# msp430g2553.net
KiCad netlist of a schematic drawn in Altium Designer
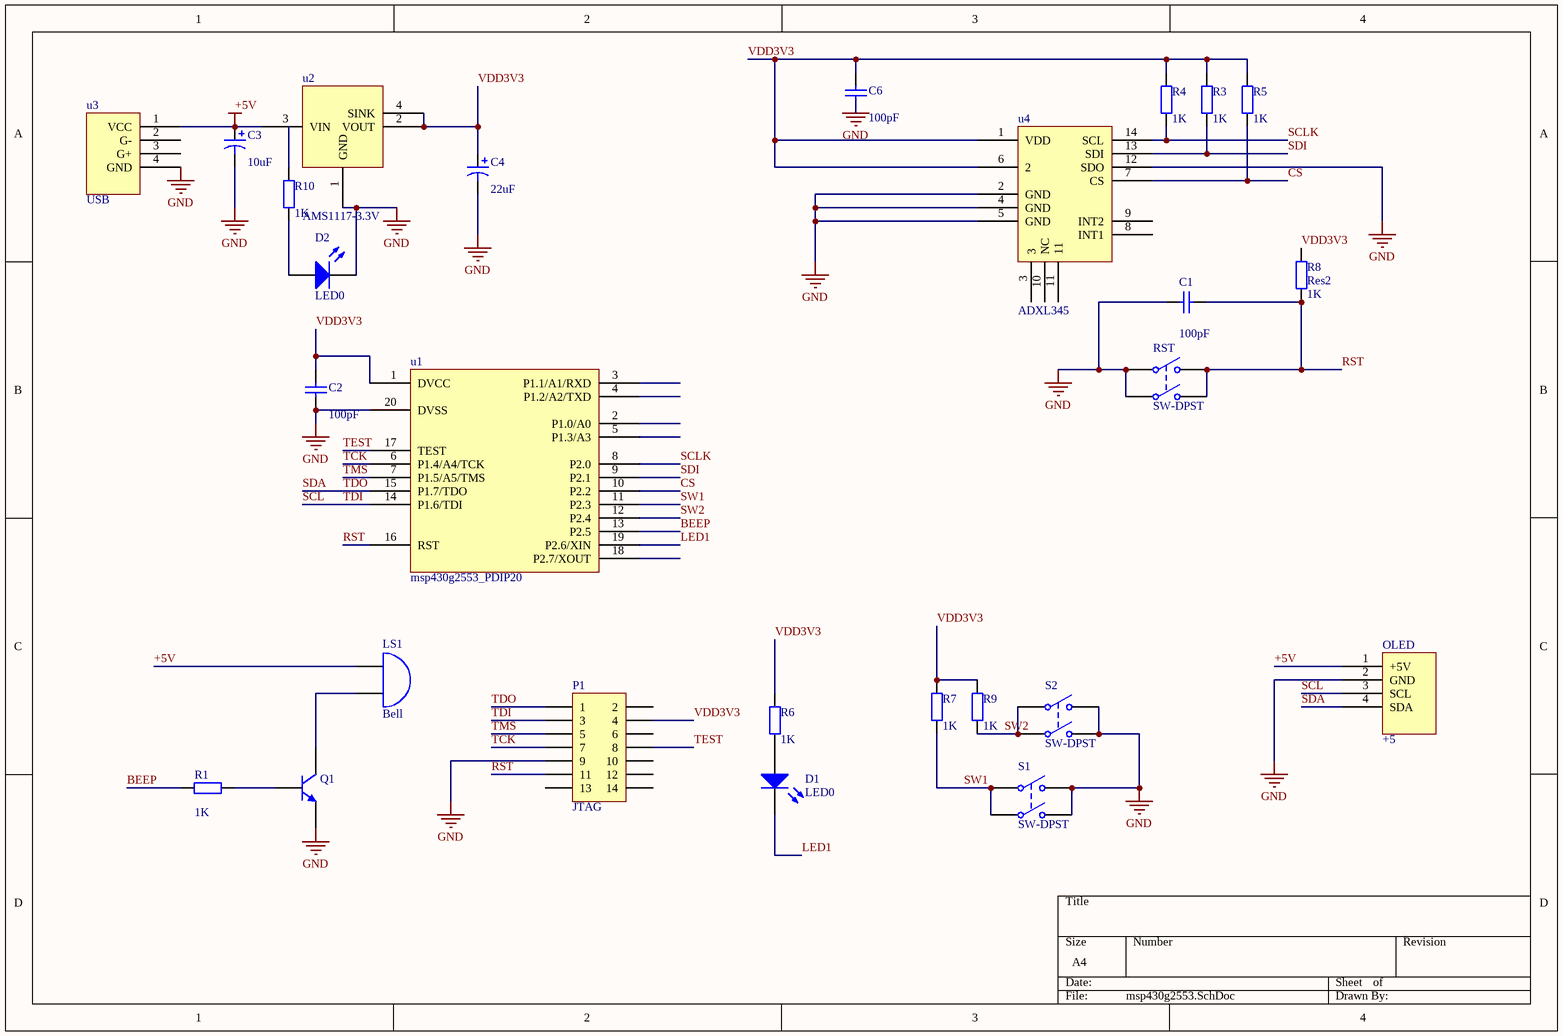
[diagram p0: msp430g2553.SchDoc]

(export (version "E")
  (design (tool "Eeschema 10.0.6"))
  (components
    (comp (ref "C1")
      (value "100pF")
      (footprint "6-0805_N")
      (description "Capacitor")
      (fields (field (name "Comment") "Cap") (field (name "PUBLISHER") "Altium Limited"))
      (libsource (lib "msp430g2553") (part "Cap"))
    )
    (comp (ref "C2")
      (value "100pF")
      (footprint "6-0805_N")
      (description "Capacitor")
      (fields (field (name "Comment") "Cap") (field (name "PUBLISHER") "Altium Limited"))
      (libsource (lib "msp430g2553") (part "Cap"))
    )
    (comp (ref "C3")
      (value "10uF")
      (footprint "6-0805_N - duplicate")
      (description "Polarized Capacitor (Axial)")
      (fields (field (name "Comment") "Cap Pol2") (field (name "PUBLISHER") "Altium Limited"))
      (libsource (lib "msp430g2553") (part "Cap Pol2"))
    )
    (comp (ref "C4")
      (value "22uF")
      (footprint "6-0805_N - duplicate")
      (description "Polarized Capacitor (Axial)")
      (fields (field (name "Comment") "Cap Pol2") (field (name "PUBLISHER") "Altium Limited"))
      (libsource (lib "msp430g2553") (part "Cap Pol2"))
    )
    (comp (ref "C6")
      (value "100pF")
      (footprint "6-0805_N")
      (description "Capacitor")
      (fields (field (name "Comment") "Cap") (field (name "PUBLISHER") "Altium Limited"))
      (libsource (lib "msp430g2553") (part "Cap"))
    )
    (comp (ref "D1")
      (value "LED0")
      (footprint "6-0805_N - duplicate")
      (description "Typical INFRARED GaAs LED")
      (fields (field (name "PUBLISHER") "Altium Limited"))
      (libsource (lib "msp430g2553") (part "LED0"))
    )
    (comp (ref "D2")
      (value "LED0")
      (footprint "6-0805_N - duplicate")
      (description "Typical INFRARED GaAs LED")
      (fields (field (name "PUBLISHER") "Altium Limited"))
      (libsource (lib "msp430g2553") (part "LED0"))
    )
    (comp (ref "LS1")
      (value "Bell")
      (footprint "bell")
      (description "Electrical Bell")
      (fields (field (name "PUBLISHER") "Altium Limited"))
      (libsource (lib "msp430g2553") (part "Bell"))
    )
    (comp (ref "OLED") (value "+5") (footprint "OLED") (libsource (lib "msp430g2553") (part "OLED")))
    (comp (ref "P1")
      (value "JTAG")
      (footprint "HDR2X7")
      (description "Header, 7-Pin, Dual row")
      (fields (field (name "PUBLISHER") "Altium Limited"))
      (libsource (lib "msp430g2553") (part "JTAG"))
    )
    (comp (ref "Q1")
      (value "NPN")
      (footprint "SOT23_N")
      (description "NPN Bipolar Transistor")
      (fields (field (name "PUBLISHER") "Altium Limited"))
      (libsource (lib "msp430g2553") (part "NPN"))
    )
    (comp (ref "R1")
      (value "1K")
      (footprint "6-0805_N")
      (description "Resistor")
      (fields (field (name "Comment") "Res2") (field (name "PUBLISHER") "Altium Limited"))
      (libsource (lib "") (part "Res2_1"))
    )
    (comp (ref "R3")
      (value "1K")
      (footprint "6-0805_N")
      (description "Resistor")
      (fields (field (name "Comment") "Res2") (field (name "PUBLISHER") "Altium Limited"))
      (libsource (lib "msp430g2553") (part "Res2"))
    )
    (comp (ref "R4")
      (value "1K")
      (footprint "6-0805_N")
      (description "Resistor")
      (fields (field (name "Comment") "Res2") (field (name "PUBLISHER") "Altium Limited"))
      (libsource (lib "msp430g2553") (part "Res2"))
    )
    (comp (ref "R5")
      (value "1K")
      (footprint "6-0805_N")
      (description "Resistor")
      (fields (field (name "Comment") "Res2") (field (name "PUBLISHER") "Altium Limited"))
      (libsource (lib "msp430g2553") (part "Res2"))
    )
    (comp (ref "R6")
      (value "1K")
      (footprint "6-0805_N")
      (description "Resistor")
      (fields (field (name "Comment") "Res2") (field (name "PUBLISHER") "Altium Limited"))
      (libsource (lib "msp430g2553") (part "Res2"))
    )
    (comp (ref "R7")
      (value "1K")
      (footprint "6-0805_N")
      (description "Resistor")
      (fields (field (name "Comment") "Res2") (field (name "PUBLISHER") "Altium Limited"))
      (libsource (lib "msp430g2553") (part "Res2"))
    )
    (comp (ref "R8")
      (value "Res2")
      (footprint "6-0805_N")
      (description "Resistor")
      (fields (field (name "ALTIUM_VALUE") "1K") (field (name "PUBLISHER") "Altium Limited"))
      (libsource (lib "msp430g2553") (part "Res2"))
    )
    (comp (ref "R9")
      (value "1K")
      (footprint "6-0805_N")
      (description "Resistor")
      (fields (field (name "Comment") "Res2") (field (name "PUBLISHER") "Altium Limited"))
      (libsource (lib "msp430g2553") (part "Res2"))
    )
    (comp (ref "R10")
      (value "1K")
      (footprint "6-0805_N")
      (description "Resistor")
      (fields (field (name "Comment") "Res2") (field (name "PUBLISHER") "Altium Limited"))
      (libsource (lib "msp430g2553") (part "Res2"))
    )
    (comp (ref "RST")
      (value "SW-DPST")
      (footprint "DPST-4")
      (description "Double-Pole, Single-Throw Switch")
      (fields (field (name "PUBLISHER") "Altium Limited"))
      (libsource (lib "msp430g2553") (part "SW-DPST"))
    )
    (comp (ref "S1")
      (value "SW-DPST")
      (footprint "DPST-4")
      (description "Double-Pole, Single-Throw Switch")
      (fields (field (name "PUBLISHER") "Altium Limited"))
      (libsource (lib "msp430g2553") (part "SW-DPST"))
    )
    (comp (ref "S2")
      (value "SW-DPST")
      (footprint "DPST-4")
      (description "Double-Pole, Single-Throw Switch")
      (fields (field (name "PUBLISHER") "Altium Limited"))
      (libsource (lib "msp430g2553") (part "SW-DPST"))
    )
    (comp (ref "u1")
      (value "msp430g2553_PDIP20")
      (footprint "DIP20")
      (libsource (lib "msp430g2553") (part "msp430g2553_PDIP20"))
    )
    (comp (ref "u2")
      (value "AMS1117-3.3V")
      (footprint "SOT223_N")
      (libsource (lib "msp430g2553") (part "AMS1117-3.3V"))
    )
    (comp (ref "u3") (value "USB") (footprint "USB2.5-2H4") (libsource (lib "msp430g2553") (part "USB")))
    (comp (ref "u4") (value "ADXL345") (footprint "ADXL345") (libsource (lib "msp430g2553") (part "ADXL345")))
  )
  (nets
    (net (code "1") (name "+5V") (class "Default")
      (node (ref "C3") (pin "2") (pinfunction "2_2") (pintype "passive"))
      (node (ref "LS1") (pin "1") (pinfunction "A_1") (pintype "passive"))
      (node (ref "OLED") (pin "1") (pinfunction "+5V_1") (pintype "passive"))
      (node (ref "u2") (pin "3") (pinfunction "VIN_3") (pintype "passive"))
      (node (ref "u3") (pin "1") (pinfunction "VCC_1") (pintype "passive"))
    )
    (net (code "2") (name "/BEEP") (class "Default")
      (node (ref "R1") (pin "1") (pinfunction "1_1") (pintype "passive"))
      (node (ref "u1") (pin "13") (pinfunction "P2.5_13") (pintype "passive"))
    )
    (net (code "3") (name "/CS") (class "Default")
      (node (ref "R5") (pin "1") (pinfunction "1_1") (pintype "passive"))
      (node (ref "u1") (pin "10") (pinfunction "P2.2_10") (pintype "passive"))
      (node (ref "u4") (pin "7") (pinfunction "CS_7") (pintype "passive"))
    )
    (net (code "4") (name "/LED1") (class "Default")
      (node (ref "D1") (pin "2") (pinfunction "K_2") (pintype "passive"))
      (node (ref "u1") (pin "19") (pinfunction "P2.6/XIN_19") (pintype "passive"))
    )
    (net (code "5") (name "/RST") (class "Default")
      (node (ref "C1") (pin "2") (pinfunction "2_2") (pintype "passive"))
      (node (ref "P1") (pin "11") (pinfunction "11_11") (pintype "passive"))
      (node (ref "R8") (pin "1") (pinfunction "1_1") (pintype "passive"))
      (node (ref "RST") (pin "3") (pinfunction "NO1_3") (pintype "passive"))
      (node (ref "RST") (pin "4") (pinfunction "NO2_4") (pintype "passive"))
      (node (ref "u1") (pin "16") (pinfunction "RST_16") (pintype "passive"))
    )
    (net (code "6") (name "/SCL") (class "Default")
      (node (ref "OLED") (pin "3") (pinfunction "SCL_3") (pintype "passive"))
      (node (ref "P1") (pin "3") (pinfunction "3_3") (pintype "passive"))
      (node (ref "u1") (pin "14") (pinfunction "P1.6/TDI_14") (pintype "passive"))
    )
    (net (code "7") (name "/SCLK") (class "Default")
      (node (ref "R4") (pin "1") (pinfunction "1_1") (pintype "passive"))
      (node (ref "u1") (pin "8") (pinfunction "P2.0_8") (pintype "passive"))
      (node (ref "u4") (pin "14") (pinfunction "SCL_14") (pintype "passive"))
    )
    (net (code "8") (name "/SDA") (class "Default")
      (node (ref "OLED") (pin "4") (pinfunction "SDA_4") (pintype "passive"))
      (node (ref "P1") (pin "1") (pinfunction "1_1") (pintype "passive"))
      (node (ref "u1") (pin "15") (pinfunction "P1.7/TDO_15") (pintype "passive"))
    )
    (net (code "9") (name "/SDI") (class "Default")
      (node (ref "R3") (pin "1") (pinfunction "1_1") (pintype "passive"))
      (node (ref "u1") (pin "9") (pinfunction "P2.1_9") (pintype "passive"))
      (node (ref "u4") (pin "13") (pinfunction "SDI_13") (pintype "passive"))
    )
    (net (code "10") (name "/SW1") (class "Default")
      (node (ref "R7") (pin "1") (pinfunction "1_1") (pintype "passive"))
      (node (ref "S1") (pin "1") (pinfunction "COMMON1_1") (pintype "passive"))
      (node (ref "S1") (pin "2") (pinfunction "COMMON2_2") (pintype "passive"))
      (node (ref "u1") (pin "11") (pinfunction "P2.3_11") (pintype "passive"))
    )
    (net (code "11") (name "/SW2") (class "Default")
      (node (ref "R9") (pin "1") (pinfunction "1_1") (pintype "passive"))
      (node (ref "S2") (pin "1") (pinfunction "COMMON1_1") (pintype "passive"))
      (node (ref "S2") (pin "2") (pinfunction "COMMON2_2") (pintype "passive"))
      (node (ref "u1") (pin "12") (pinfunction "P2.4_12") (pintype "passive"))
    )
    (net (code "12") (name "/TCK") (class "Default")
      (node (ref "P1") (pin "7") (pinfunction "7_7") (pintype "passive"))
      (node (ref "u1") (pin "6") (pinfunction "P1.4/A4/TCK_6") (pintype "passive"))
    )
    (net (code "13") (name "/TEST") (class "Default")
      (node (ref "P1") (pin "8") (pinfunction "8_8") (pintype "passive"))
      (node (ref "u1") (pin "17") (pinfunction "TEST_17") (pintype "passive"))
    )
    (net (code "14") (name "/TMS") (class "Default")
      (node (ref "P1") (pin "5") (pinfunction "5_5") (pintype "passive"))
      (node (ref "u1") (pin "7") (pinfunction "P1.5/A5/TMS_7") (pintype "passive"))
    )
    (net (code "15") (name "/VDD3V3") (class "Default")
      (node (ref "C2") (pin "2") (pinfunction "2_2") (pintype "passive"))
      (node (ref "C4") (pin "2") (pinfunction "2_2") (pintype "passive"))
      (node (ref "C6") (pin "2") (pinfunction "2_2") (pintype "passive"))
      (node (ref "P1") (pin "4") (pinfunction "4_4") (pintype "passive"))
      (node (ref "R3") (pin "2") (pinfunction "2_2") (pintype "passive"))
      (node (ref "R4") (pin "2") (pinfunction "2_2") (pintype "passive"))
      (node (ref "R5") (pin "2") (pinfunction "2_2") (pintype "passive"))
      (node (ref "R6") (pin "2") (pinfunction "2_2") (pintype "passive"))
      (node (ref "R7") (pin "2") (pinfunction "2_2") (pintype "passive"))
      (node (ref "R8") (pin "2") (pinfunction "2_2") (pintype "passive"))
      (node (ref "R9") (pin "2") (pinfunction "2_2") (pintype "passive"))
      (node (ref "u1") (pin "1") (pinfunction "DVCC_1") (pintype "passive"))
      (node (ref "u2") (pin "2") (pinfunction "VOUT_2") (pintype "passive"))
      (node (ref "u2") (pin "4") (pinfunction "SINK_4") (pintype "passive"))
      (node (ref "u4") (pin "1") (pinfunction "VDD_1") (pintype "passive"))
      (node (ref "u4") (pin "6") (pinfunction "2_6") (pintype "passive"))
    )
    (net (code "16") (name "GND") (class "Default")
      (node (ref "C1") (pin "1") (pinfunction "1_1") (pintype "passive"))
      (node (ref "C2") (pin "1") (pinfunction "1_1") (pintype "passive"))
      (node (ref "C3") (pin "1") (pinfunction "1_1") (pintype "passive"))
      (node (ref "C4") (pin "1") (pinfunction "1_1") (pintype "passive"))
      (node (ref "C6") (pin "1") (pinfunction "1_1") (pintype "passive"))
      (node (ref "D2") (pin "2") (pinfunction "K_2") (pintype "passive"))
      (node (ref "OLED") (pin "2") (pinfunction "GND_2") (pintype "passive"))
      (node (ref "P1") (pin "9") (pinfunction "9_9") (pintype "passive"))
      (node (ref "Q1") (pin "3") (pinfunction "E_3") (pintype "passive"))
      (node (ref "RST") (pin "1") (pinfunction "COMMON1_1") (pintype "passive"))
      (node (ref "RST") (pin "2") (pinfunction "COMMON2_2") (pintype "passive"))
      (node (ref "S1") (pin "3") (pinfunction "NO1_3") (pintype "passive"))
      (node (ref "S1") (pin "4") (pinfunction "NO2_4") (pintype "passive"))
      (node (ref "S2") (pin "3") (pinfunction "NO1_3") (pintype "passive"))
      (node (ref "S2") (pin "4") (pinfunction "NO2_4") (pintype "passive"))
      (node (ref "u1") (pin "20") (pinfunction "DVSS_20") (pintype "passive"))
      (node (ref "u2") (pin "1") (pinfunction "GND_1") (pintype "passive"))
      (node (ref "u3") (pin "4") (pinfunction "GND_4") (pintype "passive"))
      (node (ref "u4") (pin "12") (pinfunction "SDO_12") (pintype "passive"))
      (node (ref "u4") (pin "2") (pinfunction "GND_2") (pintype "passive"))
      (node (ref "u4") (pin "4") (pinfunction "GND_4") (pintype "passive"))
      (node (ref "u4") (pin "5") (pinfunction "GND_5") (pintype "passive"))
    )
    (net (code "17") (name "Net-(D1-A)") (class "Default")
      (node (ref "D1") (pin "1") (pinfunction "A_1") (pintype "passive"))
      (node (ref "R6") (pin "1") (pinfunction "1_1") (pintype "passive"))
    )
    (net (code "18") (name "Net-(D2-A)") (class "Default")
      (node (ref "D2") (pin "1") (pinfunction "A_1") (pintype "passive"))
      (node (ref "R10") (pin "1") (pinfunction "1_1") (pintype "passive"))
    )
    (net (code "19") (name "Net-(LS1-B)") (class "Default")
      (node (ref "LS1") (pin "2") (pinfunction "B_2") (pintype "passive"))
      (node (ref "Q1") (pin "1") (pinfunction "C_1") (pintype "passive"))
    )
    (net (code "20") (name "Net-(Q1-B)") (class "Default")
      (node (ref "Q1") (pin "2") (pinfunction "B_2") (pintype "passive"))
      (node (ref "R1") (pin "2") (pinfunction "2_2") (pintype "passive"))
    )
    (net (code "21") (name "unconnected-(P1-Pad2)") (class "Default")
      (node (ref "P1") (pin "2") (pinfunction "2_2") (pintype "passive"))
    )
    (net (code "22") (name "unconnected-(P1-Pad6)") (class "Default")
      (node (ref "P1") (pin "6") (pinfunction "6_6") (pintype "passive"))
    )
    (net (code "23") (name "unconnected-(P1-Pad10)") (class "Default")
      (node (ref "P1") (pin "10") (pinfunction "10_10") (pintype "passive"))
    )
    (net (code "24") (name "unconnected-(P1-Pad12)") (class "Default")
      (node (ref "P1") (pin "12") (pinfunction "12_12") (pintype "passive"))
    )
    (net (code "25") (name "unconnected-(P1-Pad13)") (class "Default")
      (node (ref "P1") (pin "13") (pinfunction "13_13") (pintype "passive"))
    )
    (net (code "26") (name "unconnected-(P1-Pad14)") (class "Default")
      (node (ref "P1") (pin "14") (pinfunction "14_14") (pintype "passive"))
    )
    (net (code "27") (name "unconnected-(R10-Pad2)") (class "Default")
      (node (ref "R10") (pin "2") (pinfunction "2_2") (pintype "passive"))
    )
    (net (code "28") (name "unconnected-(u1-P1.0{slash}A0-Pad2)") (class "Default")
      (node (ref "u1") (pin "2") (pinfunction "P1.0/A0_2") (pintype "passive"))
    )
    (net (code "29") (name "unconnected-(u1-P1.1{slash}A1{slash}RXD-Pad3)") (class "Default")
      (node (ref "u1") (pin "3") (pinfunction "P1.1/A1/RXD_3") (pintype "passive"))
    )
    (net (code "30") (name "unconnected-(u1-P1.2{slash}A2{slash}TXD-Pad4)") (class "Default")
      (node (ref "u1") (pin "4") (pinfunction "P1.2/A2/TXD_4") (pintype "passive"))
    )
    (net (code "31") (name "unconnected-(u1-P1.3{slash}A3-Pad5)") (class "Default")
      (node (ref "u1") (pin "5") (pinfunction "P1.3/A3_5") (pintype "passive"))
    )
    (net (code "32") (name "unconnected-(u1-P2.7{slash}XOUT-Pad18)") (class "Default")
      (node (ref "u1") (pin "18") (pinfunction "P2.7/XOUT_18") (pintype "passive"))
    )
    (net (code "33") (name "unconnected-(u3-G+-Pad3)") (class "Default")
      (node (ref "u3") (pin "3") (pinfunction "G+_3") (pintype "passive"))
    )
    (net (code "34") (name "unconnected-(u3-G--Pad2)") (class "Default")
      (node (ref "u3") (pin "2") (pinfunction "G-_2") (pintype "passive"))
    )
    (net (code "35") (name "unconnected-(u4-INT1-Pad8)") (class "Default")
      (node (ref "u4") (pin "8") (pinfunction "INT1_8") (pintype "passive"))
    )
    (net (code "36") (name "unconnected-(u4-INT2-Pad9)") (class "Default")
      (node (ref "u4") (pin "9") (pinfunction "INT2_9") (pintype "passive"))
    )
    (net (code "37") (name "unconnected-(u4-NC-Pad10)") (class "Default")
      (node (ref "u4") (pin "10") (pinfunction "NC_10") (pintype "passive"))
    )
    (net (code "38") (name "unconnected-(u4-Pad3)") (class "Default")
      (node (ref "u4") (pin "3") (pinfunction "3_3") (pintype "passive"))
    )
    (net (code "39") (name "unconnected-(u4-Pad11)") (class "Default")
      (node (ref "u4") (pin "11") (pinfunction "11_11") (pintype "passive"))
    )
  )
)
